# ME433_HW2_1.net
KiCad netlist of a schematic drawn in EAGLE
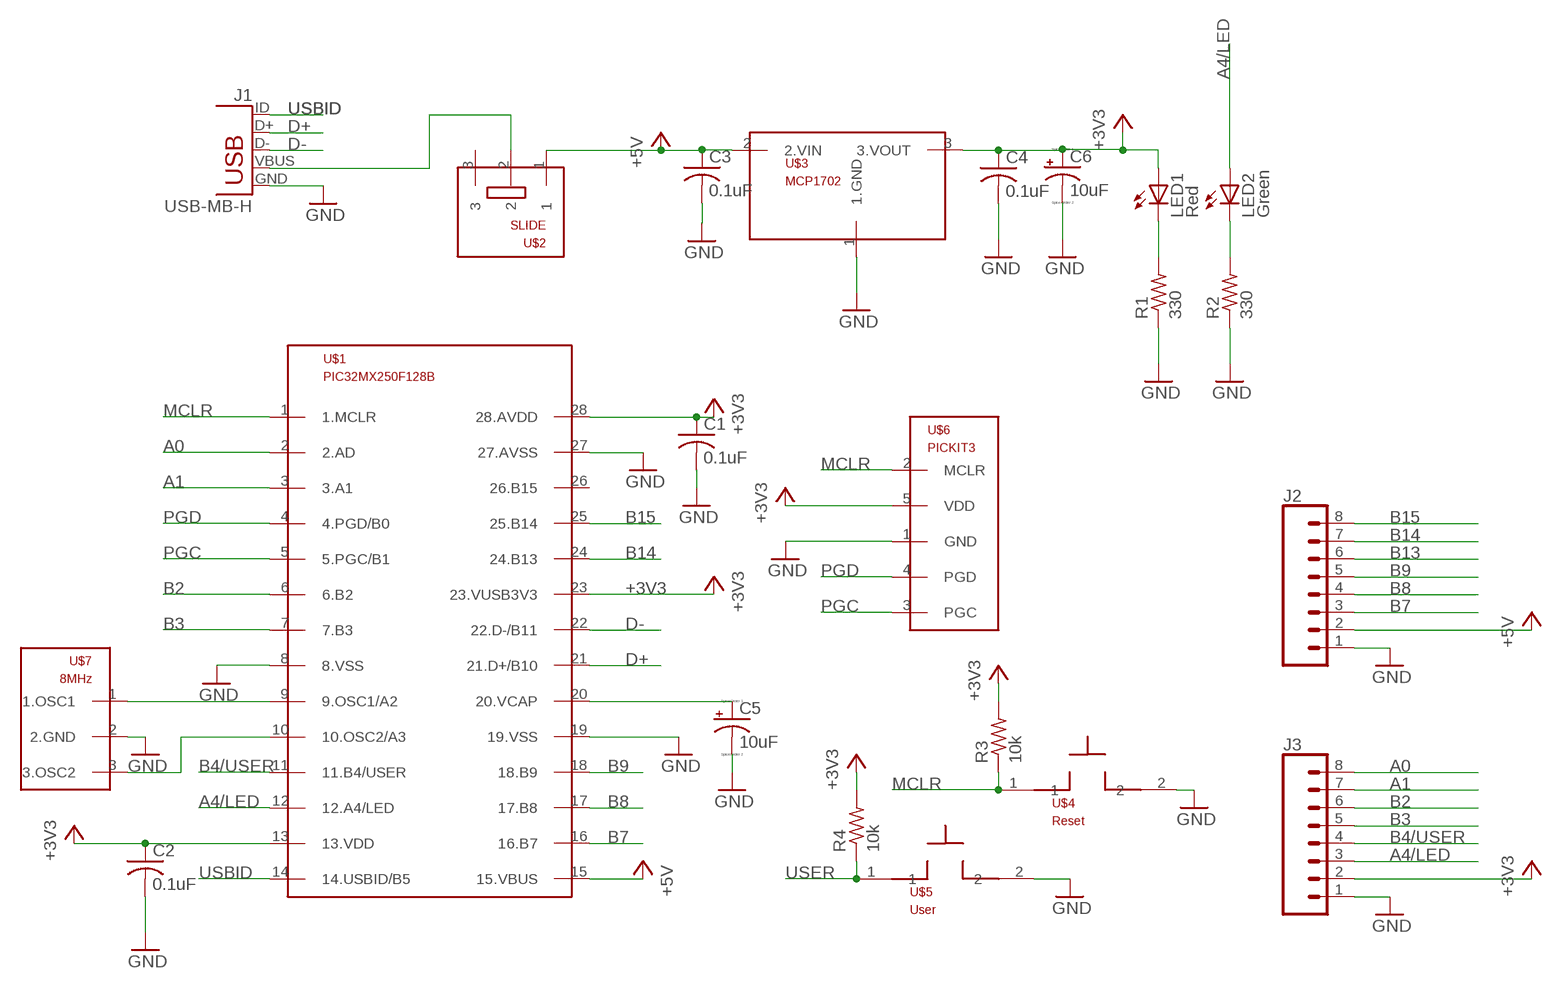
[diagram p0: schematic, sheet 1]

(export (version "E")
  (design (tool "Eeschema 10.0.6"))
  (components
    (comp (ref "C1")
      (value "0.1uF")
      (footprint "eagle-import:C025-025X050")
      (libsource (lib "eagle-import") (part "C-US025-025X050"))
    )
    (comp (ref "C2")
      (value "0.1uF")
      (footprint "eagle-import:C025-025X050")
      (libsource (lib "eagle-import") (part "C-US025-025X050"))
    )
    (comp (ref "C3")
      (value "0.1uF")
      (footprint "eagle-import:C025-025X050")
      (libsource (lib "eagle-import") (part "C-US025-025X050"))
    )
    (comp (ref "C4")
      (value "0.1uF")
      (footprint "eagle-import:C025-025X050")
      (libsource (lib "eagle-import") (part "C-US025-025X050"))
    )
    (comp (ref "C5")
      (value "10uF")
      (footprint "eagle-import:B45181B")
      (libsource (lib "eagle-import") (part "CPOL-USB45181B"))
    )
    (comp (ref "C6")
      (value "10uF")
      (footprint "eagle-import:B45181B")
      (libsource (lib "eagle-import") (part "CPOL-USB45181B"))
    )
    (comp (ref "J1")
      (value "USB-MB-H")
      (footprint "eagle-import:USB-MB-H")
      (libsource (lib "eagle-import") (part "USB-MB-H"))
    )
    (comp (ref "J2")
      (value "CONN_08\"")
      (footprint "eagle-import:1X08")
      (libsource (lib "eagle-import") (part "CONN_08{dblquote}"))
    )
    (comp (ref "J3")
      (value "CONN_08\"")
      (footprint "eagle-import:1X08")
      (libsource (lib "eagle-import") (part "CONN_08{dblquote}"))
    )
    (comp (ref "LED1")
      (value "Red")
      (footprint "eagle-import:LED3MM")
      (libsource (lib "eagle-import") (part "LED3MM"))
    )
    (comp (ref "LED2")
      (value "Green")
      (footprint "eagle-import:LED3MM")
      (libsource (lib "eagle-import") (part "LED3MM"))
    )
    (comp (ref "R1")
      (value "330")
      (footprint "eagle-import:0207_10")
      (libsource (lib "eagle-import") (part "R-US_0207/10"))
    )
    (comp (ref "R2")
      (value "330")
      (footprint "eagle-import:0207_10")
      (libsource (lib "eagle-import") (part "R-US_0207/10"))
    )
    (comp (ref "R3")
      (value "10k")
      (footprint "eagle-import:0207_10")
      (libsource (lib "eagle-import") (part "R-US_0207/10"))
    )
    (comp (ref "R4")
      (value "10k")
      (footprint "eagle-import:0207_10")
      (libsource (lib "eagle-import") (part "R-US_0207/10"))
    )
    (comp (ref "U$1")
      (value "PIC32MX250F128B")
      (footprint "eagle-import:DIL28-3")
      (libsource (lib "eagle-import") (part "PIC32MX250F128B"))
    )
    (comp (ref "U$2")
      (value "SLIDE")
      (footprint "eagle-import:SLIDE")
      (libsource (lib "eagle-import") (part "SLIDE"))
    )
    (comp (ref "U$3")
      (value "MCP1702")
      (footprint "eagle-import:TO92")
      (libsource (lib "eagle-import") (part "MCP1702"))
    )
    (comp (ref "U$4")
      (value "Reset")
      (footprint "eagle-import:PB")
      (libsource (lib "eagle-import") (part "PB"))
    )
    (comp (ref "U$5")
      (value "User")
      (footprint "eagle-import:PB")
      (libsource (lib "eagle-import") (part "PB"))
    )
    (comp (ref "U$6")
      (value "PICKIT3")
      (footprint "eagle-import:1X05")
      (libsource (lib "eagle-import") (part "PICKIT3"))
    )
    (comp (ref "U$7")
      (value "8MHz")
      (footprint "eagle-import:OSC")
      (libsource (lib "eagle-import") (part "OSC"))
    )
  )
  (nets
    (net (code "1") (name "+3V3") (class "Default")
      (node (ref "C1") (pin "1") (pinfunction "1_1") (pintype "passive"))
      (node (ref "C2") (pin "1") (pinfunction "1_1") (pintype "passive"))
      (node (ref "C4") (pin "1") (pinfunction "1_1") (pintype "passive"))
      (node (ref "C6") (pin "+") (pinfunction "+_+") (pintype "passive"))
      (node (ref "J3") (pin "2") (pinfunction "2_2") (pintype "passive"))
      (node (ref "LED1") (pin "A") (pinfunction "A_A") (pintype "passive"))
      (node (ref "R3") (pin "2") (pinfunction "2_2") (pintype "passive"))
      (node (ref "R4") (pin "2") (pinfunction "2_2") (pintype "passive"))
      (node (ref "U$1") (pin "13") (pinfunction "13.VDD_13") (pintype "bidirectional"))
      (node (ref "U$1") (pin "23") (pinfunction "23.VUSB3V3_23") (pintype "bidirectional"))
      (node (ref "U$1") (pin "28") (pinfunction "28.AVDD_28") (pintype "bidirectional"))
      (node (ref "U$3") (pin "3") (pinfunction "3.VOUT_3") (pintype "bidirectional"))
      (node (ref "U$6") (pin "5") (pinfunction "VDD_5") (pintype "bidirectional"))
    )
    (net (code "2") (name "+5V") (class "Default")
      (node (ref "C3") (pin "1") (pinfunction "1_1") (pintype "passive"))
      (node (ref "J2") (pin "2") (pinfunction "2_2") (pintype "passive"))
      (node (ref "U$1") (pin "15") (pinfunction "15.VBUS_15") (pintype "bidirectional"))
      (node (ref "U$2") (pin "1") (pinfunction "1_1") (pintype "bidirectional"))
      (node (ref "U$3") (pin "2") (pinfunction "2.VIN_2") (pintype "bidirectional"))
    )
    (net (code "3") (name "/A0") (class "Default")
      (node (ref "J3") (pin "8") (pinfunction "8_8") (pintype "passive"))
      (node (ref "U$1") (pin "2") (pinfunction "2.AD_2") (pintype "bidirectional"))
    )
    (net (code "4") (name "/A1") (class "Default")
      (node (ref "J3") (pin "7") (pinfunction "7_7") (pintype "passive"))
      (node (ref "U$1") (pin "3") (pinfunction "3.A1_3") (pintype "bidirectional"))
    )
    (net (code "5") (name "/A4{slash}LED") (class "Default")
      (node (ref "J3") (pin "3") (pinfunction "3_3") (pintype "passive"))
      (node (ref "LED2") (pin "A") (pinfunction "A_A") (pintype "passive"))
      (node (ref "U$1") (pin "12") (pinfunction "12.A4/LED_12") (pintype "bidirectional"))
    )
    (net (code "6") (name "/B2") (class "Default")
      (node (ref "J3") (pin "6") (pinfunction "6_6") (pintype "passive"))
      (node (ref "U$1") (pin "6") (pinfunction "6.B2_6") (pintype "bidirectional"))
    )
    (net (code "7") (name "/B3") (class "Default")
      (node (ref "J3") (pin "5") (pinfunction "5_5") (pintype "passive"))
      (node (ref "U$1") (pin "7") (pinfunction "7.B3_7") (pintype "bidirectional"))
    )
    (net (code "8") (name "/B4{slash}USER") (class "Default")
      (node (ref "J3") (pin "4") (pinfunction "4_4") (pintype "passive"))
      (node (ref "U$1") (pin "11") (pinfunction "11.B4/USER_11") (pintype "bidirectional"))
    )
    (net (code "9") (name "/B7") (class "Default")
      (node (ref "J2") (pin "3") (pinfunction "3_3") (pintype "passive"))
      (node (ref "U$1") (pin "16") (pinfunction "16.B7_16") (pintype "bidirectional"))
    )
    (net (code "10") (name "/B8") (class "Default")
      (node (ref "J2") (pin "4") (pinfunction "4_4") (pintype "passive"))
      (node (ref "U$1") (pin "17") (pinfunction "17.B8_17") (pintype "bidirectional"))
    )
    (net (code "11") (name "/B9") (class "Default")
      (node (ref "J2") (pin "5") (pinfunction "5_5") (pintype "passive"))
      (node (ref "U$1") (pin "18") (pinfunction "18.B9_18") (pintype "bidirectional"))
    )
    (net (code "12") (name "/B13") (class "Default")
      (node (ref "J2") (pin "6") (pinfunction "6_6") (pintype "passive"))
    )
    (net (code "13") (name "/B14") (class "Default")
      (node (ref "J2") (pin "7") (pinfunction "7_7") (pintype "passive"))
      (node (ref "U$1") (pin "24") (pinfunction "24.B13_24") (pintype "bidirectional"))
    )
    (net (code "14") (name "/B15") (class "Default")
      (node (ref "J2") (pin "8") (pinfunction "8_8") (pintype "passive"))
      (node (ref "U$1") (pin "25") (pinfunction "25.B14_25") (pintype "bidirectional"))
    )
    (net (code "15") (name "/D+") (class "Default")
      (node (ref "J1") (pin "D+") (pinfunction "D+_D+") (pintype "bidirectional"))
      (node (ref "U$1") (pin "21") (pinfunction "21.D+/B10_21") (pintype "bidirectional"))
    )
    (net (code "16") (name "/D-") (class "Default")
      (node (ref "J1") (pin "D-") (pinfunction "D-_D-") (pintype "bidirectional"))
      (node (ref "U$1") (pin "22") (pinfunction "22.D-/B11_22") (pintype "bidirectional"))
    )
    (net (code "17") (name "/MCLR") (class "Default")
      (node (ref "R3") (pin "1") (pinfunction "1_1") (pintype "passive"))
      (node (ref "U$1") (pin "1") (pinfunction "1.MCLR_1") (pintype "bidirectional"))
      (node (ref "U$4") (pin "1") (pinfunction "1_1") (pintype "bidirectional"))
      (node (ref "U$6") (pin "2") (pinfunction "MCLR_2") (pintype "bidirectional"))
    )
    (net (code "18") (name "/PGC") (class "Default")
      (node (ref "U$1") (pin "5") (pinfunction "5.PGC/B1_5") (pintype "bidirectional"))
      (node (ref "U$6") (pin "3") (pinfunction "PGC_3") (pintype "bidirectional"))
    )
    (net (code "19") (name "/PGD") (class "Default")
      (node (ref "U$1") (pin "4") (pinfunction "4.PGD/B0_4") (pintype "bidirectional"))
      (node (ref "U$6") (pin "4") (pinfunction "PGD_4") (pintype "bidirectional"))
    )
    (net (code "20") (name "/USBID") (class "Default")
      (node (ref "J1") (pin "ID") (pinfunction "ID_ID") (pintype "bidirectional"))
      (node (ref "U$1") (pin "14") (pinfunction "14.USBID/B5_14") (pintype "bidirectional"))
    )
    (net (code "21") (name "/USER") (class "Default")
      (node (ref "R4") (pin "1") (pinfunction "1_1") (pintype "passive"))
      (node (ref "U$5") (pin "1") (pinfunction "1_1") (pintype "bidirectional"))
    )
    (net (code "22") (name "GND") (class "Default")
      (node (ref "C1") (pin "2") (pinfunction "2_2") (pintype "passive"))
      (node (ref "C2") (pin "2") (pinfunction "2_2") (pintype "passive"))
      (node (ref "C3") (pin "2") (pinfunction "2_2") (pintype "passive"))
      (node (ref "C4") (pin "2") (pinfunction "2_2") (pintype "passive"))
      (node (ref "C5") (pin "-") (pinfunction "-_-") (pintype "passive"))
      (node (ref "C6") (pin "-") (pinfunction "-_-") (pintype "passive"))
      (node (ref "J1") (pin "GND") (pinfunction "GND_GND") (pintype "bidirectional"))
      (node (ref "J2") (pin "1") (pinfunction "1_1") (pintype "passive"))
      (node (ref "J3") (pin "1") (pinfunction "1_1") (pintype "passive"))
      (node (ref "R1") (pin "1") (pinfunction "1_1") (pintype "passive"))
      (node (ref "R2") (pin "1") (pinfunction "1_1") (pintype "passive"))
      (node (ref "U$1") (pin "19") (pinfunction "19.VSS_19") (pintype "bidirectional"))
      (node (ref "U$1") (pin "27") (pinfunction "27.AVSS_27") (pintype "bidirectional"))
      (node (ref "U$1") (pin "8") (pinfunction "8.VSS_8") (pintype "bidirectional"))
      (node (ref "U$3") (pin "1") (pinfunction "1.GND_1") (pintype "bidirectional"))
      (node (ref "U$4") (pin "2") (pinfunction "2_2") (pintype "bidirectional"))
      (node (ref "U$5") (pin "2") (pinfunction "2_2") (pintype "bidirectional"))
      (node (ref "U$6") (pin "1") (pinfunction "GND_1") (pintype "bidirectional"))
      (node (ref "U$7") (pin "2") (pinfunction "2.GND_2") (pintype "bidirectional"))
    )
    (net (code "23") (name "Net-(J1-PadVBUS)") (class "Default")
      (node (ref "J1") (pin "VBUS") (pinfunction "VBUS_VBUS") (pintype "bidirectional"))
      (node (ref "U$2") (pin "2") (pinfunction "2_2") (pintype "bidirectional"))
    )
    (net (code "24") (name "Net-(LED1-C)") (class "Default")
      (node (ref "LED1") (pin "K") (pinfunction "C_K") (pintype "passive"))
      (node (ref "R1") (pin "2") (pinfunction "2_2") (pintype "passive"))
    )
    (net (code "25") (name "Net-(LED2-C)") (class "Default")
      (node (ref "LED2") (pin "K") (pinfunction "C_K") (pintype "passive"))
      (node (ref "R2") (pin "2") (pinfunction "2_2") (pintype "passive"))
    )
    (net (code "26") (name "Net-(U$1-9.OSC1{slash}A2)") (class "Default")
      (node (ref "U$1") (pin "9") (pinfunction "9.OSC1/A2_9") (pintype "bidirectional"))
      (node (ref "U$7") (pin "1") (pinfunction "1.OSC1_1") (pintype "bidirectional"))
    )
    (net (code "27") (name "Net-(U$1-10.OSC2{slash}A3)") (class "Default")
      (node (ref "U$1") (pin "10") (pinfunction "10.OSC2/A3_10") (pintype "bidirectional"))
      (node (ref "U$7") (pin "3") (pinfunction "3.OSC2_3") (pintype "bidirectional"))
    )
    (net (code "28") (name "Net-(U$1-20.VCAP)") (class "Default")
      (node (ref "C5") (pin "+") (pinfunction "+_+") (pintype "passive"))
      (node (ref "U$1") (pin "20") (pinfunction "20.VCAP_20") (pintype "bidirectional"))
    )
    (net (code "29") (name "unconnected-(U$1-26.B15-Pad26)") (class "Default")
      (node (ref "U$1") (pin "26") (pinfunction "26.B15_26") (pintype "bidirectional"))
    )
    (net (code "30") (name "unconnected-(U$2-Pad3)") (class "Default")
      (node (ref "U$2") (pin "3") (pinfunction "3_3") (pintype "bidirectional"))
    )
  )
)
